# Main.net
KiCad netlist of a schematic drawn in Altium Designer
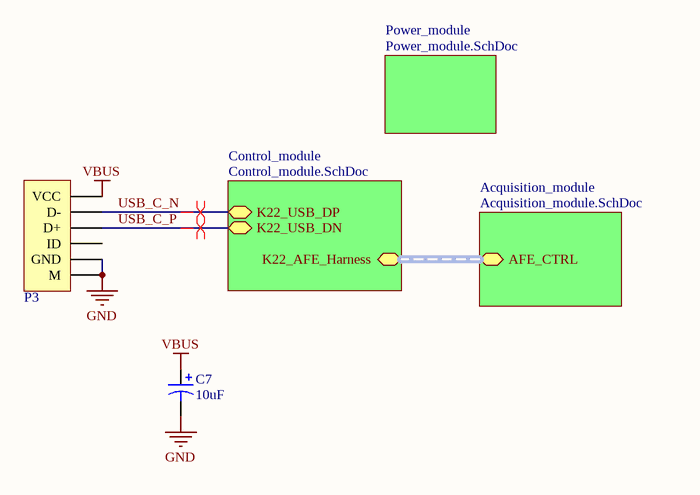
[diagram p0: Main.SchDoc]

(export (version "E")
  (design (tool "Eeschema 10.0.6"))
  (components
    (comp (ref "C7")
      (value "10uF")
      (footprint "CAP SMD 4mm")
      (description "Polarized Capacitor (Radial)")
      (fields (field (name "Comment") "Cap Pol1") (field (name "PUBLISHER") "Altium Limited"))
      (libsource (lib "Miscellaneous Devices") (part "Cap Pol1"))
    )
    (comp (ref "P3")
      (value "USB Header")
      (footprint "MicroUSB-B")
      (fields (field (name "PUBLISHER") "Altium Limited"))
      (libsource (lib "connectors") (part "USB 7 pin Header"))
    )
  )
  (nets
    (net (code "2") (name "/USB_C_N") (class "Default")
      (node (ref "P3") (pin "D-") (pinfunction "D-_D-") (pintype "passive"))
    )
    (net (code "3") (name "/USB_C_P") (class "Default")
      (node (ref "P3") (pin "D+") (pinfunction "D+_D+") (pintype "passive"))
    )
    (net (code "4") (name "GND") (class "Default")
      (node (ref "C7") (pin "2") (pinfunction "2_2") (pintype "passive"))
      (node (ref "P3") (pin "GND") (pinfunction "GND_GND") (pintype "passive"))
      (node (ref "P3") (pin "M") (pinfunction "M_M") (pintype "passive"))
    )
    (net (code "5") (name "VBUS") (class "Default")
      (node (ref "C7") (pin "1") (pinfunction "1_1") (pintype "passive"))
      (node (ref "P3") (pin "VCC") (pinfunction "VCC_VCC") (pintype "passive"))
    )
    (net (code "6") (name "unconnected-(P3-PadID)") (class "Default")
      (node (ref "P3") (pin "ID") (pinfunction "ID_ID") (pintype "passive"))
    )
  )
)
